# controller_v1_1B.net
KiCad netlist of a schematic drawn in EAGLE
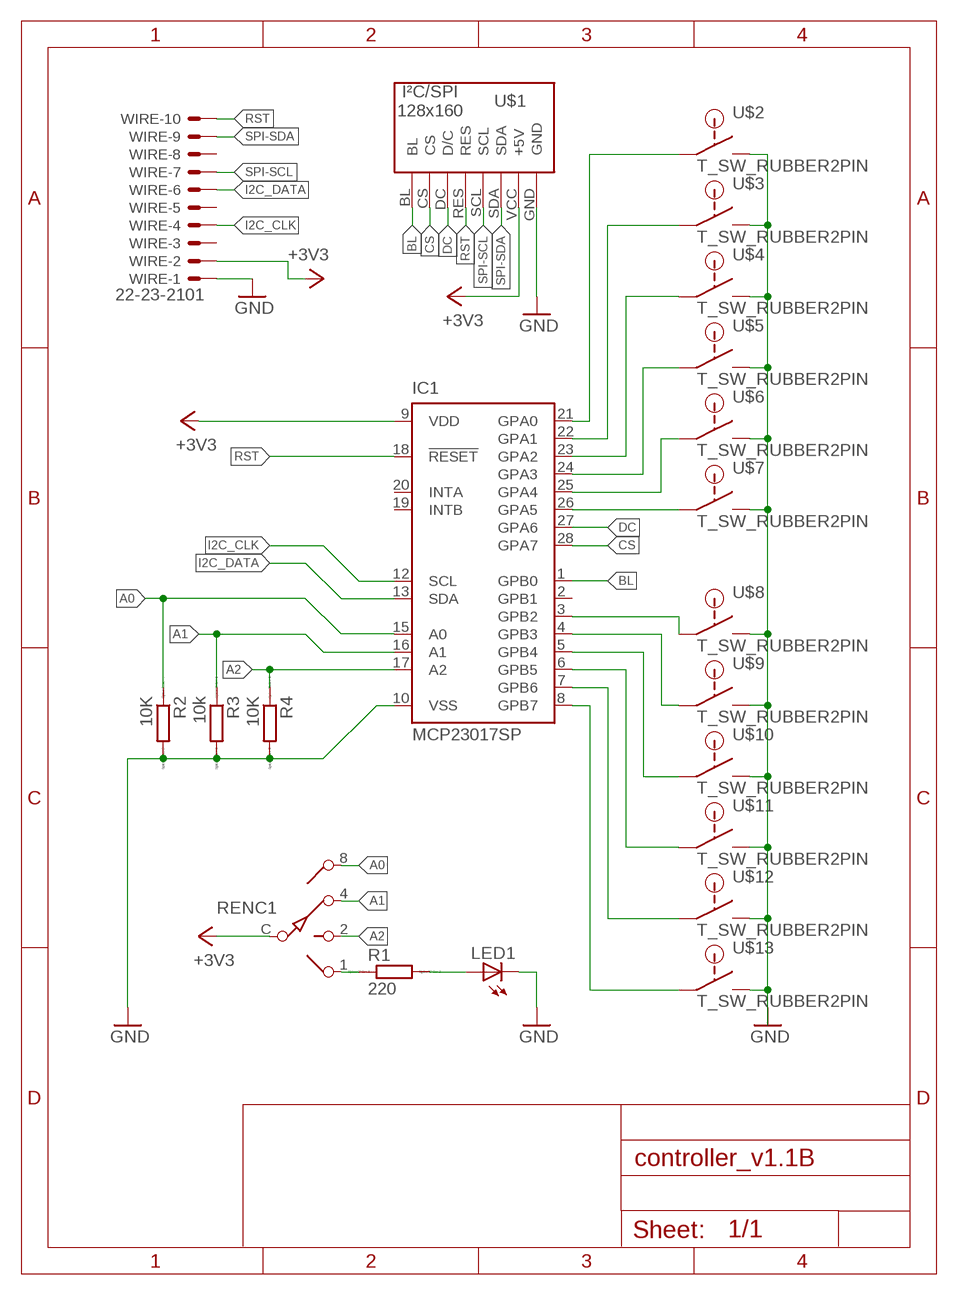
[diagram p0: schematic, sheet 1]

(export (version "E")
  (design (tool "Eeschema 10.0.6"))
  (components
    (comp (ref "IC1")
      (value "MCP23017SP")
      (footprint "eagle-import:DIL28-3")
      (fields (field (name "MF") "MICROCHIP") (field (name "MPN") "MCP23017-E/SP"))
      (libsource (lib "eagle-import") (part "MCP23017SP"))
    )
    (comp (ref "LED1")
      (value "LED3MM")
      (footprint "eagle-import:LED3MM")
      (libsource (lib "eagle-import") (part "LED3MM"))
    )
    (comp (ref "R1")
      (value "220")
      (footprint "eagle-import:0207_10")
      (libsource (lib "eagle-import") (part "R0207/10"))
    )
    (comp (ref "R2")
      (value "10K")
      (footprint "eagle-import:0207_10")
      (libsource (lib "eagle-import") (part "R0207/10"))
    )
    (comp (ref "R3")
      (value "10k")
      (footprint "eagle-import:0207_10")
      (libsource (lib "eagle-import") (part "R0207/10"))
    )
    (comp (ref "R4")
      (value "10K")
      (footprint "eagle-import:0207_10")
      (libsource (lib "eagle-import") (part "R0207/10"))
    )
    (comp (ref "RENC1")
      (value "SW-C10")
      (footprint "eagle-import:SW-C10")
      (libsource (lib "eagle-import") (part "SW-C10"))
    )
    (comp (ref "U$1")
      (value "ST7735_128X160")
      (footprint "eagle-import:128X160_ST7735")
      (libsource (lib "eagle-import") (part "ST7735_128X160"))
    )
    (comp (ref "U$2")
      (value "T_SW_RUBBER2PIN")
      (footprint "eagle-import:2PIN")
      (libsource (lib "eagle-import") (part "T_SW_RUBBER2PIN"))
    )
    (comp (ref "U$3")
      (value "T_SW_RUBBER2PIN")
      (footprint "eagle-import:2PIN")
      (libsource (lib "eagle-import") (part "T_SW_RUBBER2PIN"))
    )
    (comp (ref "U$4")
      (value "T_SW_RUBBER2PIN")
      (footprint "eagle-import:2PIN")
      (libsource (lib "eagle-import") (part "T_SW_RUBBER2PIN"))
    )
    (comp (ref "U$5")
      (value "T_SW_RUBBER2PIN")
      (footprint "eagle-import:2PIN")
      (libsource (lib "eagle-import") (part "T_SW_RUBBER2PIN"))
    )
    (comp (ref "U$6")
      (value "T_SW_RUBBER2PIN")
      (footprint "eagle-import:2PIN")
      (libsource (lib "eagle-import") (part "T_SW_RUBBER2PIN"))
    )
    (comp (ref "U$7")
      (value "T_SW_RUBBER2PIN")
      (footprint "eagle-import:2PIN")
      (libsource (lib "eagle-import") (part "T_SW_RUBBER2PIN"))
    )
    (comp (ref "U$8")
      (value "T_SW_RUBBER2PIN")
      (footprint "eagle-import:2PIN")
      (libsource (lib "eagle-import") (part "T_SW_RUBBER2PIN"))
    )
    (comp (ref "U$9")
      (value "T_SW_RUBBER2PIN")
      (footprint "eagle-import:2PIN")
      (libsource (lib "eagle-import") (part "T_SW_RUBBER2PIN"))
    )
    (comp (ref "U$10")
      (value "T_SW_RUBBER2PIN")
      (footprint "eagle-import:2PIN")
      (libsource (lib "eagle-import") (part "T_SW_RUBBER2PIN"))
    )
    (comp (ref "U$11")
      (value "T_SW_RUBBER2PIN")
      (footprint "eagle-import:2PIN")
      (libsource (lib "eagle-import") (part "T_SW_RUBBER2PIN"))
    )
    (comp (ref "U$12")
      (value "T_SW_RUBBER2PIN")
      (footprint "eagle-import:2PIN")
      (libsource (lib "eagle-import") (part "T_SW_RUBBER2PIN"))
    )
    (comp (ref "U$13")
      (value "T_SW_RUBBER2PIN")
      (footprint "eagle-import:2PIN")
      (libsource (lib "eagle-import") (part "T_SW_RUBBER2PIN"))
    )
    (comp (ref "WIRE")
      (value "22-23-2101")
      (footprint "eagle-import:22-23-2101")
      (fields (field (name "MF") "MOLEX") (field (name "MPN") "Wire-connection"))
      (libsource (lib "eagle-import") (part "22-23-2101"))
    )
  )
  (nets
    (net (code "1") (name "+3V3") (class "Default")
      (node (ref "IC1") (pin "9") (pinfunction "VDD_9") (pintype "power_in"))
      (node (ref "RENC1") (pin "C") (pinfunction "C_C") (pintype "passive"))
      (node (ref "U$1") (pin "VCC") (pinfunction "+5V_VCC") (pintype "bidirectional"))
      (node (ref "WIRE") (pin "2") (pinfunction "S_2") (pintype "passive"))
    )
    (net (code "2") (name "A0") (class "Default")
      (node (ref "IC1") (pin "15") (pinfunction "A0_15") (pintype "input"))
      (node (ref "R2") (pin "1") (pinfunction "1_1") (pintype "passive"))
      (node (ref "RENC1") (pin "8") (pinfunction "8_8") (pintype "passive"))
    )
    (net (code "3") (name "A1") (class "Default")
      (node (ref "IC1") (pin "16") (pinfunction "A1_16") (pintype "input"))
      (node (ref "R3") (pin "1") (pinfunction "1_1") (pintype "passive"))
      (node (ref "RENC1") (pin "4") (pinfunction "4_4") (pintype "passive"))
    )
    (net (code "4") (name "A2") (class "Default")
      (node (ref "IC1") (pin "17") (pinfunction "A2_17") (pintype "input"))
      (node (ref "R4") (pin "1") (pinfunction "1_1") (pintype "passive"))
      (node (ref "RENC1") (pin "2") (pinfunction "2_2") (pintype "passive"))
    )
    (net (code "5") (name "BL") (class "Default")
      (node (ref "IC1") (pin "1") (pinfunction "GPB0_1") (pintype "bidirectional"))
      (node (ref "U$1") (pin "BL") (pinfunction "BL_BL") (pintype "bidirectional"))
    )
    (net (code "6") (name "CS") (class "Default")
      (node (ref "IC1") (pin "28") (pinfunction "GPA7_28") (pintype "bidirectional"))
      (node (ref "U$1") (pin "CS") (pinfunction "CS_CS") (pintype "bidirectional"))
    )
    (net (code "7") (name "DC") (class "Default")
      (node (ref "IC1") (pin "27") (pinfunction "GPA6_27") (pintype "bidirectional"))
      (node (ref "U$1") (pin "DC") (pinfunction "D/C_DC") (pintype "bidirectional"))
    )
    (net (code "8") (name "GND") (class "Default")
      (node (ref "IC1") (pin "10") (pinfunction "VSS_10") (pintype "power_in"))
      (node (ref "LED1") (pin "K") (pinfunction "C_K") (pintype "passive"))
      (node (ref "R2") (pin "2") (pinfunction "2_2") (pintype "passive"))
      (node (ref "R3") (pin "2") (pinfunction "2_2") (pintype "passive"))
      (node (ref "R4") (pin "2") (pinfunction "2_2") (pintype "passive"))
      (node (ref "U$1") (pin "GND") (pinfunction "GND_GND") (pintype "bidirectional"))
      (node (ref "U$10") (pin "P$3") (pinfunction "P$2_P$3") (pintype "bidirectional"))
      (node (ref "U$11") (pin "P$3") (pinfunction "P$2_P$3") (pintype "bidirectional"))
      (node (ref "U$12") (pin "P$3") (pinfunction "P$2_P$3") (pintype "bidirectional"))
      (node (ref "U$13") (pin "P$3") (pinfunction "P$2_P$3") (pintype "bidirectional"))
      (node (ref "U$2") (pin "P$3") (pinfunction "P$2_P$3") (pintype "bidirectional"))
      (node (ref "U$3") (pin "P$3") (pinfunction "P$2_P$3") (pintype "bidirectional"))
      (node (ref "U$4") (pin "P$3") (pinfunction "P$2_P$3") (pintype "bidirectional"))
      (node (ref "U$5") (pin "P$3") (pinfunction "P$2_P$3") (pintype "bidirectional"))
      (node (ref "U$6") (pin "P$3") (pinfunction "P$2_P$3") (pintype "bidirectional"))
      (node (ref "U$7") (pin "P$3") (pinfunction "P$2_P$3") (pintype "bidirectional"))
      (node (ref "U$8") (pin "P$3") (pinfunction "P$2_P$3") (pintype "bidirectional"))
      (node (ref "U$9") (pin "P$3") (pinfunction "P$2_P$3") (pintype "bidirectional"))
      (node (ref "WIRE") (pin "1") (pinfunction "S_1") (pintype "passive"))
    )
    (net (code "9") (name "I2C_CLK") (class "Default")
      (node (ref "IC1") (pin "12") (pinfunction "SCL_12") (pintype "input"))
      (node (ref "WIRE") (pin "4") (pinfunction "S_4") (pintype "passive"))
    )
    (net (code "10") (name "I2C_DATA") (class "Default")
      (node (ref "IC1") (pin "13") (pinfunction "SDA_13") (pintype "bidirectional"))
      (node (ref "WIRE") (pin "6") (pinfunction "S_6") (pintype "passive"))
    )
    (net (code "11") (name "Net-(IC1-GPA0)") (class "Default")
      (node (ref "IC1") (pin "21") (pinfunction "GPA0_21") (pintype "bidirectional"))
      (node (ref "U$2") (pin "P$2") (pinfunction "P$1_P$2") (pintype "bidirectional"))
    )
    (net (code "12") (name "Net-(IC1-GPA1)") (class "Default")
      (node (ref "IC1") (pin "22") (pinfunction "GPA1_22") (pintype "bidirectional"))
      (node (ref "U$3") (pin "P$2") (pinfunction "P$1_P$2") (pintype "bidirectional"))
    )
    (net (code "13") (name "Net-(IC1-GPA2)") (class "Default")
      (node (ref "IC1") (pin "23") (pinfunction "GPA2_23") (pintype "bidirectional"))
      (node (ref "U$4") (pin "P$2") (pinfunction "P$1_P$2") (pintype "bidirectional"))
    )
    (net (code "14") (name "Net-(IC1-GPA3)") (class "Default")
      (node (ref "IC1") (pin "24") (pinfunction "GPA3_24") (pintype "bidirectional"))
      (node (ref "U$5") (pin "P$2") (pinfunction "P$1_P$2") (pintype "bidirectional"))
    )
    (net (code "15") (name "Net-(IC1-GPA4)") (class "Default")
      (node (ref "IC1") (pin "25") (pinfunction "GPA4_25") (pintype "bidirectional"))
      (node (ref "U$6") (pin "P$2") (pinfunction "P$1_P$2") (pintype "bidirectional"))
    )
    (net (code "16") (name "Net-(IC1-GPA5)") (class "Default")
      (node (ref "IC1") (pin "26") (pinfunction "GPA5_26") (pintype "bidirectional"))
      (node (ref "U$7") (pin "P$2") (pinfunction "P$1_P$2") (pintype "bidirectional"))
    )
    (net (code "17") (name "Net-(IC1-GPB2)") (class "Default")
      (node (ref "IC1") (pin "3") (pinfunction "GPB2_3") (pintype "bidirectional"))
      (node (ref "U$8") (pin "P$2") (pinfunction "P$1_P$2") (pintype "bidirectional"))
    )
    (net (code "18") (name "Net-(IC1-GPB3)") (class "Default")
      (node (ref "IC1") (pin "4") (pinfunction "GPB3_4") (pintype "bidirectional"))
      (node (ref "U$9") (pin "P$2") (pinfunction "P$1_P$2") (pintype "bidirectional"))
    )
    (net (code "19") (name "Net-(IC1-GPB4)") (class "Default")
      (node (ref "IC1") (pin "5") (pinfunction "GPB4_5") (pintype "bidirectional"))
      (node (ref "U$10") (pin "P$2") (pinfunction "P$1_P$2") (pintype "bidirectional"))
    )
    (net (code "20") (name "Net-(IC1-GPB5)") (class "Default")
      (node (ref "IC1") (pin "6") (pinfunction "GPB5_6") (pintype "bidirectional"))
      (node (ref "U$11") (pin "P$2") (pinfunction "P$1_P$2") (pintype "bidirectional"))
    )
    (net (code "21") (name "Net-(IC1-GPB6)") (class "Default")
      (node (ref "IC1") (pin "7") (pinfunction "GPB6_7") (pintype "bidirectional"))
      (node (ref "U$12") (pin "P$2") (pinfunction "P$1_P$2") (pintype "bidirectional"))
    )
    (net (code "22") (name "Net-(IC1-GPB7)") (class "Default")
      (node (ref "IC1") (pin "8") (pinfunction "GPB7_8") (pintype "bidirectional"))
      (node (ref "U$13") (pin "P$2") (pinfunction "P$1_P$2") (pintype "bidirectional"))
    )
    (net (code "23") (name "Net-(LED1-PadA)") (class "Default")
      (node (ref "LED1") (pin "A") (pinfunction "A_A") (pintype "passive"))
      (node (ref "R1") (pin "2") (pinfunction "2_2") (pintype "passive"))
    )
    (net (code "24") (name "Net-(R1-Pad1)") (class "Default")
      (node (ref "R1") (pin "1") (pinfunction "1_1") (pintype "passive"))
      (node (ref "RENC1") (pin "1") (pinfunction "1_1") (pintype "passive"))
    )
    (net (code "25") (name "RST") (class "Default")
      (node (ref "IC1") (pin "18") (pinfunction "~{RESET}_18") (pintype "input"))
      (node (ref "U$1") (pin "RES") (pinfunction "RES_RES") (pintype "bidirectional"))
      (node (ref "WIRE") (pin "10") (pinfunction "S_10") (pintype "passive"))
    )
    (net (code "26") (name "SPI-SCL") (class "Default")
      (node (ref "U$1") (pin "SCL") (pinfunction "SCL_SCL") (pintype "bidirectional"))
      (node (ref "WIRE") (pin "7") (pinfunction "S_7") (pintype "passive"))
    )
    (net (code "27") (name "SPI-SDA") (class "Default")
      (node (ref "U$1") (pin "SDA") (pinfunction "SDA_SDA") (pintype "bidirectional"))
      (node (ref "WIRE") (pin "9") (pinfunction "S_9") (pintype "passive"))
    )
    (net (code "28") (name "unconnected-(IC1-GPB1-Pad2)") (class "Default")
      (node (ref "IC1") (pin "2") (pinfunction "GPB1_2") (pintype "bidirectional"))
    )
    (net (code "29") (name "unconnected-(IC1-INTA-Pad20)") (class "Default")
      (node (ref "IC1") (pin "20") (pinfunction "INTA_20") (pintype "output"))
    )
    (net (code "30") (name "unconnected-(IC1-INTB-Pad19)") (class "Default")
      (node (ref "IC1") (pin "19") (pinfunction "INTB_19") (pintype "output"))
    )
    (net (code "31") (name "unconnected-(WIRED-S-Pad3)") (class "Default")
      (node (ref "WIRE") (pin "3") (pinfunction "S_3") (pintype "passive"))
    )
    (net (code "32") (name "unconnected-(WIREF-S-Pad5)") (class "Default")
      (node (ref "WIRE") (pin "5") (pinfunction "S_5") (pintype "passive"))
    )
    (net (code "33") (name "unconnected-(WIREI-S-Pad8)") (class "Default")
      (node (ref "WIRE") (pin "8") (pinfunction "S_8") (pintype "passive"))
    )
  )
)
